# Regensensor.net
KiCad netlist of a schematic drawn in EAGLE
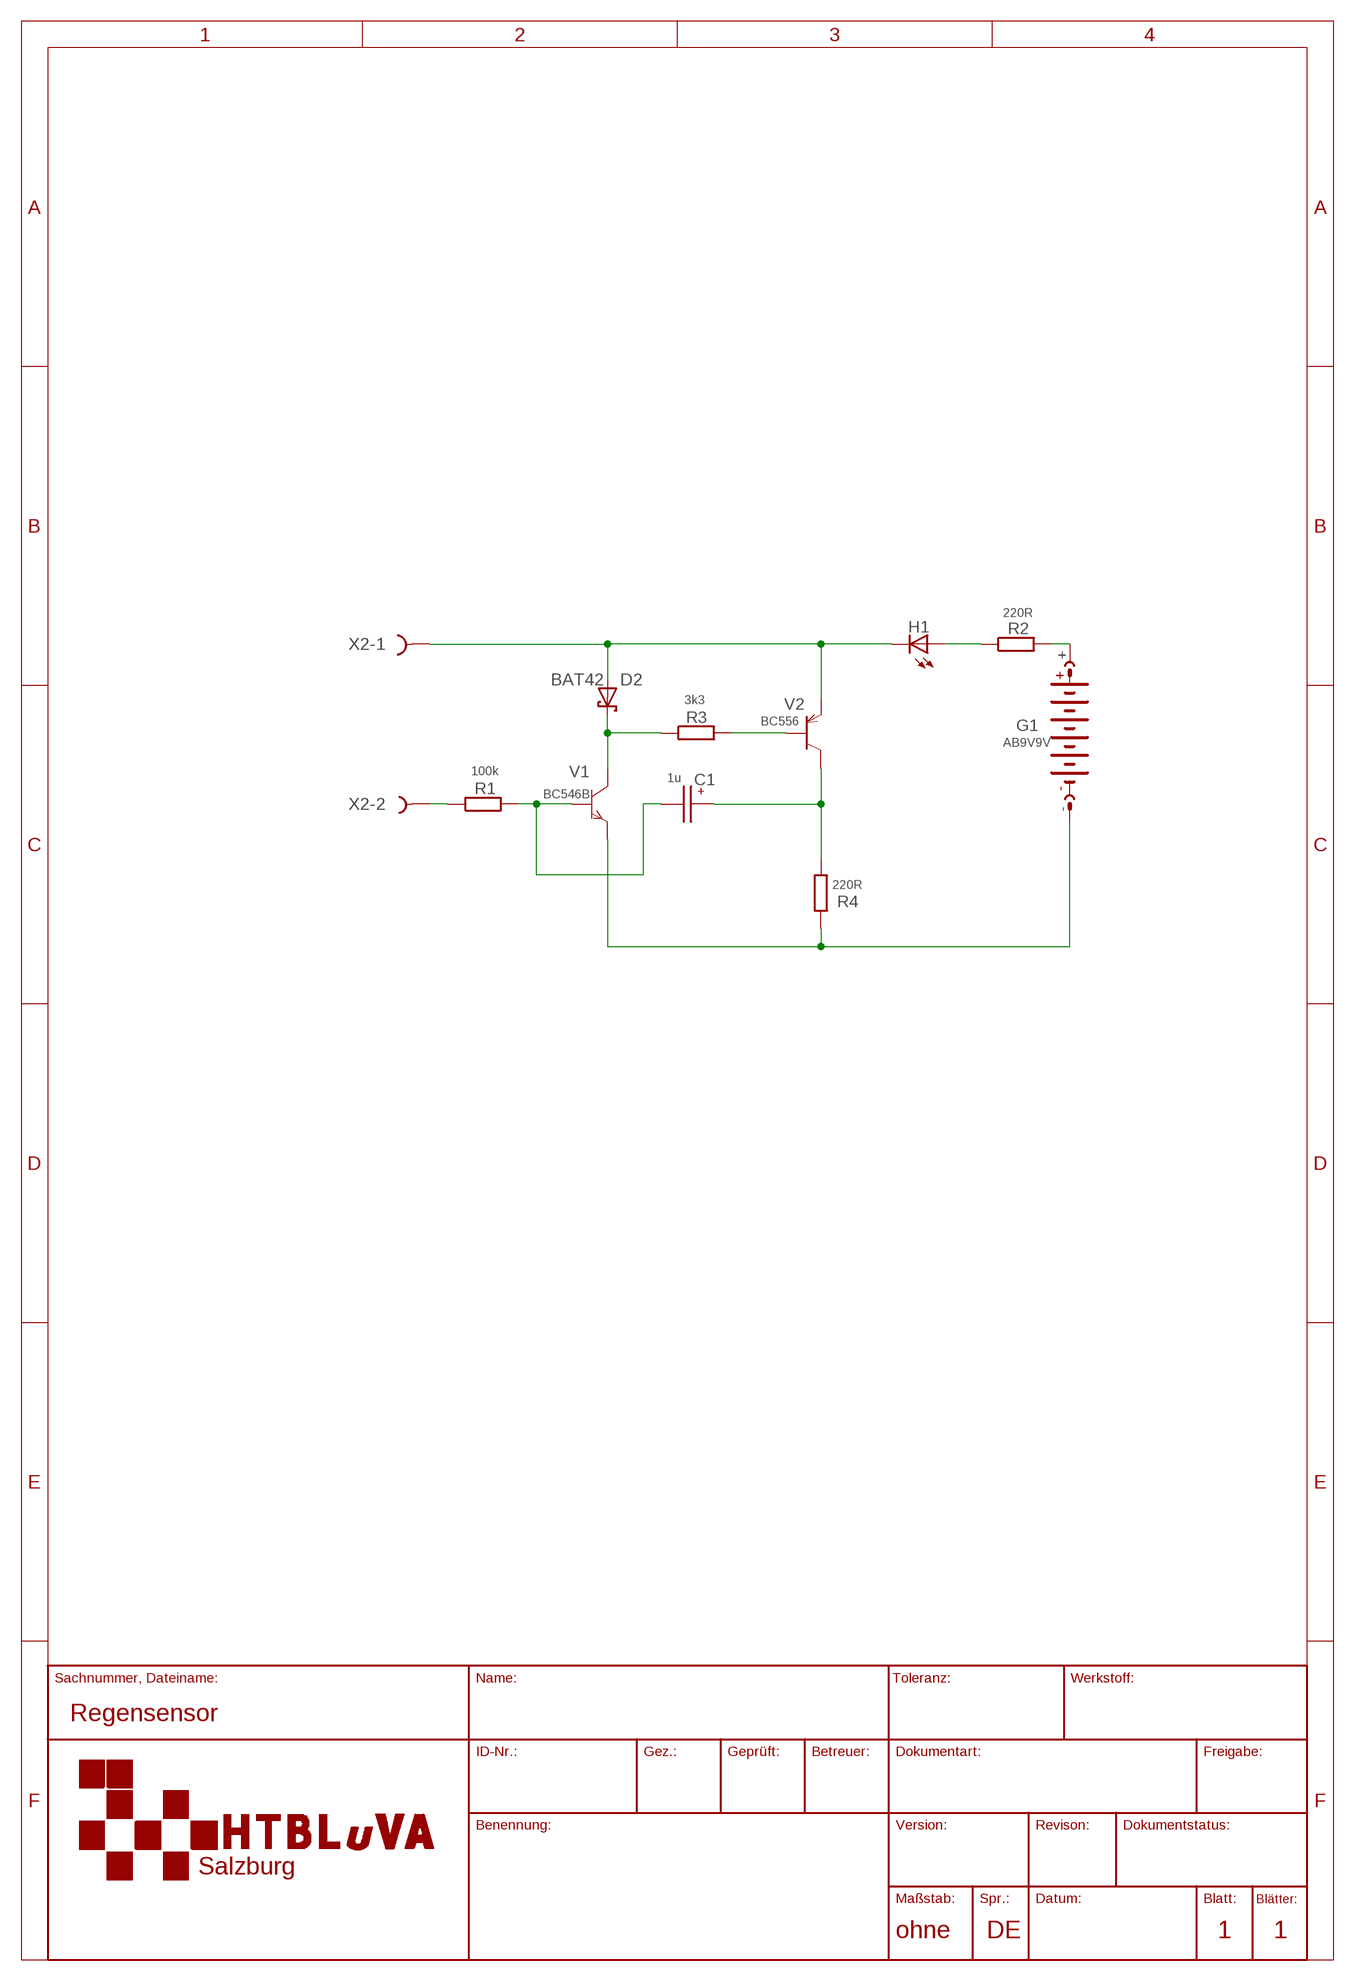
[diagram p0: schematic, sheet 1]

(export (version "E")
  (design (tool "Eeschema 10.0.6"))
  (components
    (comp (ref "C1")
      (value "1u")
      (footprint "eagle-import:E2-5")
      (libsource (lib "eagle-import") (part "CPOL-V_E2-5"))
    )
    (comp (ref "D2")
      (value "BAT42")
      (footprint "eagle-import:DO35-10")
      (libsource (lib "eagle-import") (part "BAT42"))
    )
    (comp (ref "G1")
      (value "AB9V9V")
      (footprint "eagle-import:AB9V")
      (libsource (lib "eagle-import") (part "AB9V9V"))
    )
    (comp (ref "H1")
      (value "LED_3MM")
      (footprint "eagle-import:LED3MM")
      (libsource (lib "eagle-import") (part "LED_3MM"))
    )
    (comp (ref "R1")
      (value "100k")
      (footprint "eagle-import:0309_12")
      (libsource (lib "eagle-import") (part "R-H_0309/12"))
    )
    (comp (ref "R2")
      (value "220R")
      (footprint "eagle-import:0309_12")
      (libsource (lib "eagle-import") (part "R-H_0309/12"))
    )
    (comp (ref "R3")
      (value "3k3")
      (footprint "eagle-import:0309_12")
      (libsource (lib "eagle-import") (part "R-H_0309/12"))
    )
    (comp (ref "R4")
      (value "220R")
      (footprint "eagle-import:0309_12")
      (libsource (lib "eagle-import") (part "R-H_0309/12"))
    )
    (comp (ref "V1")
      (value "BC546B")
      (footprint "eagle-import:TO92-EBC")
      (libsource (lib "eagle-import") (part "BC546B"))
    )
    (comp (ref "V2")
      (value "BC556")
      (footprint "eagle-import:TO92-EBC")
      (libsource (lib "eagle-import") (part "BC556"))
    )
    (comp (ref "X2")
      (value "W237-02P")
      (footprint "eagle-import:W237-132")
      (libsource (lib "eagle-import") (part "W237-02P"))
    )
  )
  (nets
    (net (code "1") (name "Net-(C1-Pad+)") (class "Default")
      (node (ref "C1") (pin "+") (pinfunction "+_+") (pintype "passive"))
      (node (ref "R4") (pin "1") (pinfunction "1_1") (pintype "passive"))
      (node (ref "V2") (pin "C") (pinfunction "C_C") (pintype "passive"))
    )
    (net (code "2") (name "Net-(C1-Pad-)") (class "Default")
      (node (ref "C1") (pin "-") (pinfunction "-_-") (pintype "passive"))
      (node (ref "R1") (pin "2") (pinfunction "2_2") (pintype "passive"))
      (node (ref "V1") (pin "B") (pinfunction "B_B") (pintype "passive"))
    )
    (net (code "3") (name "Net-(D2-PadC)") (class "Default")
      (node (ref "D2") (pin "C") (pinfunction "C_C") (pintype "passive"))
      (node (ref "R3") (pin "1") (pinfunction "1_1") (pintype "passive"))
      (node (ref "V1") (pin "C") (pinfunction "C_C") (pintype "passive"))
    )
    (net (code "4") (name "Net-(G1-Pad+)") (class "Default")
      (node (ref "G1") (pin "+") (pinfunction "+_+") (pintype "passive"))
      (node (ref "R2") (pin "2") (pinfunction "2_2") (pintype "passive"))
    )
    (net (code "5") (name "Net-(G1-Pad-)") (class "Default")
      (node (ref "G1") (pin "-") (pinfunction "-_-") (pintype "passive"))
      (node (ref "R4") (pin "2") (pinfunction "2_2") (pintype "passive"))
      (node (ref "V1") (pin "E") (pinfunction "E_E") (pintype "passive"))
    )
    (net (code "6") (name "Net-(H1-C)") (class "Default")
      (node (ref "D2") (pin "A") (pinfunction "A_A") (pintype "passive"))
      (node (ref "H1") (pin "K") (pinfunction "C_K") (pintype "passive"))
      (node (ref "V2") (pin "E") (pinfunction "E_E") (pintype "passive"))
      (node (ref "X2") (pin "1") (pinfunction "KL_1") (pintype "passive"))
    )
    (net (code "7") (name "Net-(H1-PadA)") (class "Default")
      (node (ref "H1") (pin "A") (pinfunction "A_A") (pintype "passive"))
      (node (ref "R2") (pin "1") (pinfunction "1_1") (pintype "passive"))
    )
    (net (code "8") (name "Net-(R3-Pad2)") (class "Default")
      (node (ref "R3") (pin "2") (pinfunction "2_2") (pintype "passive"))
      (node (ref "V2") (pin "B") (pinfunction "B_B") (pintype "passive"))
    )
    (net (code "9") (name "Net-(X2B-KL)") (class "Default")
      (node (ref "R1") (pin "1") (pinfunction "1_1") (pintype "passive"))
      (node (ref "X2") (pin "2") (pinfunction "KL_2") (pintype "passive"))
    )
  )
)
